# REPORT_flussimetro.net
KiCad netlist of a schematic drawn in EAGLE
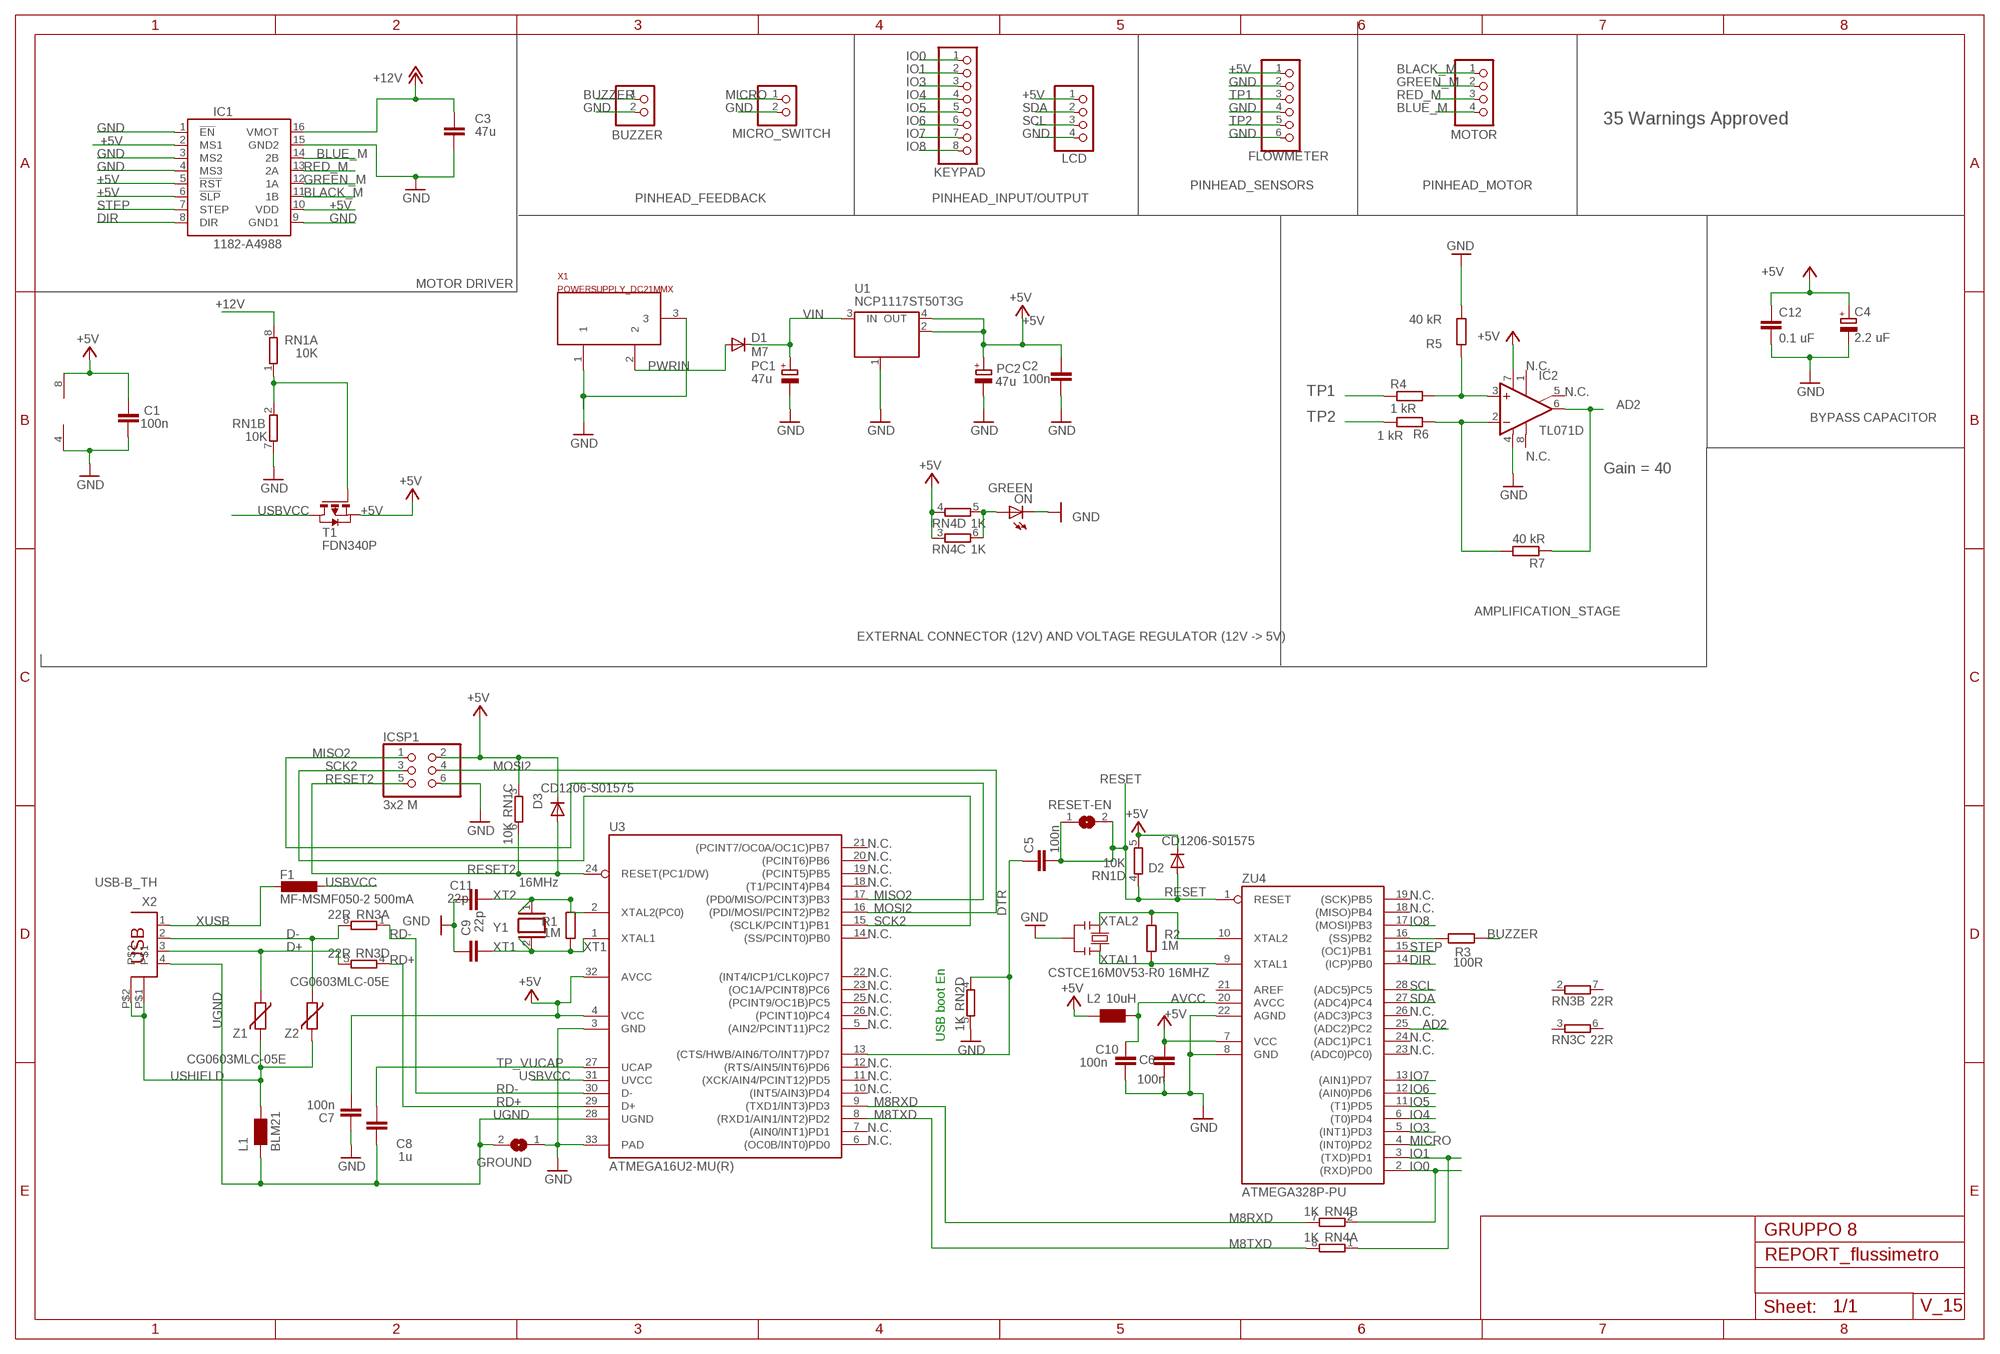
[diagram p0: schematic, sheet 1]

(export (version "E")
  (design (tool "Eeschema 10.0.6"))
  (components
    (comp (ref "BUZZER")
      (value "PINHD-1X2")
      (footprint "eagle-import:1X02")
      (fields (field (name "MF") "AMP - TE CONNECTIVITY") (field (name "MPN") "826926-2"))
      (libsource (lib "eagle-import") (part "PINHD-1X2"))
    )
    (comp (ref "C1")
      (value "100n")
      (footprint "eagle-import:C0603-ROUND")
      (fields (field (name "MF") "GEDORE") (field (name "MPN") "4550-10"))
      (libsource (lib "eagle-import") (part "C-EU0603-RND"))
    )
    (comp (ref "C2")
      (value "100n")
      (footprint "eagle-import:C0603-ROUND")
      (fields (field (name "MF") "GEDORE") (field (name "MPN") "4550-10"))
      (libsource (lib "eagle-import") (part "C-EU0603-RND"))
    )
    (comp (ref "C3")
      (value "47u")
      (footprint "eagle-import:C0603")
      (fields (field (name "MF") "MURATA") (field (name "MPN") "GRM188R60J476ME15D"))
      (libsource (lib "eagle-import") (part "rcl_334_C-EUC0603"))
    )
    (comp (ref "C4")
      (value "2.2 uF")
      (footprint "eagle-import:A_3216-18R")
      (fields (field (name "MF") "KYOCERA AVX") (field (name "MPN") "TAJA225K016RNJ"))
      (libsource (lib "eagle-import") (part "rcl_334_CPOL-EUA/3216-18R"))
    )
    (comp (ref "C5")
      (value "100n")
      (footprint "eagle-import:C0603-ROUND")
      (fields (field (name "MF") "GEDORE") (field (name "MPN") "4550-10"))
      (libsource (lib "eagle-import") (part "C-EU0603-RND"))
    )
    (comp (ref "C6")
      (value "100n")
      (footprint "eagle-import:C0603-ROUND")
      (fields (field (name "MF") "GEDORE") (field (name "MPN") "4550-10"))
      (libsource (lib "eagle-import") (part "C-EU0603-RND"))
    )
    (comp (ref "C7")
      (value "100n")
      (footprint "eagle-import:C0603-ROUND")
      (fields (field (name "MF") "GEDORE") (field (name "MPN") "4550-10"))
      (libsource (lib "eagle-import") (part "C-EU0603-RND"))
    )
    (comp (ref "C8")
      (value "1u")
      (footprint "eagle-import:C0603-ROUND")
      (fields (field (name "MF") "TDK") (field (name "MPN") "C1608X5R1C105K080AA"))
      (libsource (lib "eagle-import") (part "C-EU0603-RND"))
    )
    (comp (ref "C9")
      (value "22p")
      (footprint "eagle-import:C0603-ROUND")
      (fields (field (name "MF") "KYOCERA AVX") (field (name "MPN") "06035A220FAT2A"))
      (libsource (lib "eagle-import") (part "C-EU0603-RND"))
    )
    (comp (ref "C10")
      (value "100n")
      (footprint "eagle-import:C0603-ROUND")
      (fields (field (name "MF") "GEDORE") (field (name "MPN") "4550-10"))
      (libsource (lib "eagle-import") (part "C-EU0603-RND"))
    )
    (comp (ref "C11")
      (value "22p")
      (footprint "eagle-import:C0603-ROUND")
      (fields (field (name "MF") "KYOCERA AVX") (field (name "MPN") "06035A220FAT2A"))
      (libsource (lib "eagle-import") (part "C-EU0603-RND"))
    )
    (comp (ref "C12")
      (value "0.1 uF")
      (footprint "eagle-import:C0603")
      (fields (field (name "MF") "KYOCERA AVX") (field (name "MPN") "0603YC104KAT2A"))
      (libsource (lib "eagle-import") (part "rcl_334_C-EUC0603"))
    )
    (comp (ref "D1")
      (value "M7")
      (footprint "eagle-import:SMB")
      (fields (field (name "MF") "DIODES INC.") (field (name "MPN") "S1M-13-F"))
      (libsource (lib "eagle-import") (part "DIODE-SMB"))
    )
    (comp (ref "D2")
      (value "CD1206-S01575")
      (footprint "eagle-import:MINIMELF")
      (fields (field (name "MF") "BOURNS"))
      (libsource (lib "eagle-import") (part "DIODE-MINIMELF"))
    )
    (comp (ref "D3")
      (value "CD1206-S01575")
      (footprint "eagle-import:MINIMELF")
      (fields (field (name "MF") "BOURNS"))
      (libsource (lib "eagle-import") (part "DIODE-MINIMELF"))
    )
    (comp (ref "F1")
      (value "MF-MSMF050-2 500mA")
      (footprint "eagle-import:L1812")
      (fields (field (name "MF") "BOURNS") (field (name "MPN") "MF-MSMF050-2"))
      (libsource (lib "eagle-import") (part "L-EUL1812"))
    )
    (comp (ref "FLOWMETER")
      (value "PINHD-1X6")
      (footprint "eagle-import:1X06")
      (fields (field (name "MF") "MULTICOMP PRO") (field (name "MPN") "2211S-06G"))
      (libsource (lib "eagle-import") (part "PINHD-1X6"))
    )
    (comp (ref "GROUND")
      (value "SJ")
      (footprint "eagle-import:SJ")
      (libsource (lib "eagle-import") (part "SJ"))
    )
    (comp (ref "IC1")
      (value "1182-A4988")
      (footprint "eagle-import:A4988")
      (libsource (lib "eagle-import") (part "1182-A4988"))
    )
    (comp (ref "IC2")
      (value "TL071D")
      (footprint "eagle-import:SO08")
      (fields (field (name "MF") "ANALOG DEVICES") (field (name "MPN") "LT1211CS8#TRPBF"))
      (libsource (lib "eagle-import") (part "TL071D"))
    )
    (comp (ref "ICSP1")
      (value "3x2 M")
      (footprint "eagle-import:2X03")
      (fields (field (name "MF") "MOLEX") (field (name "MPN") "87758-0616"))
      (libsource (lib "eagle-import") (part "PINHD-2X3"))
    )
    (comp (ref "KEYPAD")
      (value "PINHD-1X8")
      (footprint "eagle-import:1X08")
      (fields (field (name "MF") "MULTICOMP PRO") (field (name "MPN") "2211S-08G"))
      (libsource (lib "eagle-import") (part "PINHD-1X8"))
    )
    (comp (ref "L1")
      (value "BLM21")
      (footprint "eagle-import:0805")
      (fields (field (name "MF") "MURATA") (field (name "MPN") "BLM21SP471BH1D"))
      (libsource (lib "eagle-import") (part "WE-CBF_0805"))
    )
    (comp (ref "L2")
      (value "10uH")
      (footprint "eagle-import:0805")
      (fields (field (name "PART_NUMBER") "CV201210-100K") (field (name "MF") "BOURNS"))
      (libsource (lib "eagle-import") (part "0715_CV201210-100K"))
    )
    (comp (ref "LCD")
      (value "PINHD-1X4")
      (footprint "eagle-import:1X04")
      (fields (field (name "MF") "AMP - TE CONNECTIVITY") (field (name "MPN") "826926-4"))
      (libsource (lib "eagle-import") (part "PINHD-1X4"))
    )
    (comp (ref "MICRO_SWITCH")
      (value "PINHD-1X2")
      (footprint "eagle-import:1X02")
      (fields (field (name "MF") "AMP - TE CONNECTIVITY") (field (name "MPN") "826926-2"))
      (libsource (lib "eagle-import") (part "PINHD-1X2"))
    )
    (comp (ref "MOTOR")
      (value "PINHD-1X4")
      (footprint "eagle-import:1X04")
      (fields (field (name "MF") "AMP - TE CONNECTIVITY") (field (name "MPN") "826926-4"))
      (libsource (lib "eagle-import") (part "PINHD-1X4"))
    )
    (comp (ref "ON")
      (value "GREEN")
      (footprint "eagle-import:CHIP-LED0805")
      (fields (field (name "MF") "KINGBRIGHT") (field (name "MPN") "KP-1608SGC"))
      (libsource (lib "eagle-import") (part "LEDCHIP-LED0805"))
    )
    (comp (ref "PC1")
      (value "47u")
      (footprint "eagle-import:PANASONIC_D")
      (fields (field (name "MF") "PANASONIC") (field (name "MPN") "EEE1EA470WP"))
      (libsource (lib "eagle-import") (part "CPOL-EUD"))
    )
    (comp (ref "PC2")
      (value "47u")
      (footprint "eagle-import:PANASONIC_D")
      (fields (field (name "MF") "PANASONIC") (field (name "MPN") "EEE1EA470WP"))
      (libsource (lib "eagle-import") (part "CPOL-EUD"))
    )
    (comp (ref "R1")
      (value "1M")
      (footprint "eagle-import:R0603-ROUND")
      (fields (field (name "MF") "TE CONNECTIVITY") (field (name "MPN") "CRGH0603J1M0"))
      (libsource (lib "eagle-import") (part "R-EU_R0603"))
    )
    (comp (ref "R2")
      (value "1M")
      (footprint "eagle-import:R0603-ROUND")
      (fields (field (name "MF") "TE CONNECTIVITY") (field (name "MPN") "CRGH0603J1M0"))
      (libsource (lib "eagle-import") (part "R-EU_R0603"))
    )
    (comp (ref "R3")
      (value "100R")
      (footprint "eagle-import:R0603")
      (fields (field (name "MF") "PANASONIC") (field (name "MPN") "ERJPA3F1000V"))
      (libsource (lib "eagle-import") (part "rcl_334_R-EU_R0603"))
    )
    (comp (ref "R4")
      (value "1 kR")
      (footprint "eagle-import:R0603")
      (fields (field (name "MF") "NEOHM - TE CONNECTIVITY") (field (name "MPN") "CPF0603B1K0E1"))
      (libsource (lib "eagle-import") (part "rcl_334_R-EU_R0603"))
    )
    (comp (ref "R5")
      (value "40 kR")
      (footprint "eagle-import:R0603")
      (fields (field (name "MF") "YAGEO") (field (name "MPN") "AT0603BRD0740KL"))
      (libsource (lib "eagle-import") (part "rcl_334_R-EU_R0603"))
    )
    (comp (ref "R6")
      (value "1 kR")
      (footprint "eagle-import:R0603")
      (fields (field (name "MF") "NEOHM - TE CONNECTIVITY") (field (name "MPN") "CPF0603B1K0E1"))
      (libsource (lib "eagle-import") (part "rcl_334_R-EU_R0603"))
    )
    (comp (ref "R7")
      (value "40 kR")
      (footprint "eagle-import:R0603")
      (fields (field (name "MF") "YAGEO") (field (name "MPN") "AT0603BRD0740KL"))
      (libsource (lib "eagle-import") (part "rcl_334_R-EU_R0603"))
    )
    (comp (ref "RESET-EN")
      (value "SJ")
      (footprint "eagle-import:SJ")
      (libsource (lib "eagle-import") (part "SJ"))
    )
    (comp (ref "RN1")
      (value "10K")
      (footprint "eagle-import:CAY16")
      (fields
        (field (name "MF") "BOURNS")
        (field (name "MPN") "CAY16-1002F4LF")
        (field (name "OC_FARNELL") "1770143")
      )
      (libsource (lib "eagle-import") (part "4R-NCAY16"))
    )
    (comp (ref "RN2")
      (value "1K")
      (footprint "eagle-import:CAY16")
      (fields (field (name "MF") "BOURNS") (field (name "MPN") "CAY16-102J4LF"))
      (libsource (lib "eagle-import") (part "4R-NCAY16"))
    )
    (comp (ref "RN3")
      (value "22R")
      (footprint "eagle-import:CAY16")
      (fields
        (field (name "MF") "BOURNS")
        (field (name "MPN") "CAY16-220J4LF")
        (field (name "OC_FARNELL") "1770127")
      )
      (libsource (lib "eagle-import") (part "4R-NCAY16"))
    )
    (comp (ref "RN4")
      (value "1K")
      (footprint "eagle-import:CAY16")
      (fields
        (field (name "MF") "BOURNS")
        (field (name "MPN") "CAY16-102J4LF")
        (field (name "OC_FARNELL") "1770133")
      )
      (libsource (lib "eagle-import") (part "4R-NCAY16"))
    )
    (comp (ref "T1")
      (value "FDN340P")
      (footprint "eagle-import:SOT-23")
      (fields (field (name "MF") "ONSEMI"))
      (libsource (lib "eagle-import") (part "PMOSSOT23"))
    )
    (comp (ref "U1")
      (value "NCP1117ST50T3G")
      (footprint "eagle-import:SOT223")
      (fields (field (name "MF") "ONSEMI"))
      (libsource (lib "eagle-import") (part "MC33269ST-3.3T3"))
    )
    (comp (ref "U3")
      (value "ATMEGA16U2-MU(R)")
      (footprint "eagle-import:MLF32")
      (fields (field (name "MF") "MICROCHIP") (field (name "MPN") "ATMEGA16U2-MUR"))
      (libsource (lib "eagle-import") (part "ATMEGA16U2-MU"))
    )
    (comp (ref "U5")
      (value "LMV358IDGKR")
      (footprint "eagle-import:MSOP08")
      (fields (field (name "MF") "STMICROELECTRONICS") (field (name "MPN") "LMV358LIST"))
      (libsource (lib "eagle-import") (part "LMV358?MMX"))
    )
    (comp (ref "X1")
      (value "POWERSUPPLY_DC21MMX")
      (footprint "eagle-import:POWERSUPPLY_DC-21MM")
      (fields (field (name "MF") "LUMBERG") (field (name "MPN") "1613 21"))
      (libsource (lib "eagle-import") (part "POWERSUPPLY_DC21MMX"))
    )
    (comp (ref "X2")
      (value "USB-B_TH")
      (footprint "eagle-import:PN61729")
      (fields (field (name "MF") "MULTICOMP PRO") (field (name "MPN") "SPC4937"))
      (libsource (lib "eagle-import") (part "PN61729"))
    )
    (comp (ref "Y1")
      (value "16MHz")
      (footprint "eagle-import:QS")
      (fields (field (name "MF") "ECS INC INTERNATIONAL") (field (name "MPN") "ECS-160-20-4X"))
      (libsource (lib "eagle-import") (part "XTAL/S"))
    )
    (comp (ref "Y2")
      (value "CSTCE16M0V53-R0 16MHZ")
      (footprint "eagle-import:RESONATOR")
      (fields (field (name "MF") "MURATA") (field (name "MPN") "CSTNE16M0V51C000R0"))
      (libsource (lib "eagle-import") (part "RESONATORMU"))
    )
    (comp (ref "Z1")
      (value "CG0603MLC-05E")
      (footprint "eagle-import:CT_CN0603")
      (fields (field (name "MF") "BOURNS"))
      (libsource (lib "eagle-import") (part "VARISTORCN0603"))
    )
    (comp (ref "Z2")
      (value "CG0603MLC-05E")
      (footprint "eagle-import:CT_CN0603")
      (fields (field (name "MF") "BOURNS"))
      (libsource (lib "eagle-import") (part "VARISTORCN0603"))
    )
    (comp (ref "ZU4")
      (value "ATMEGA328P-PU")
      (footprint "eagle-import:DIL28-3")
      (fields (field (name "MF") "MICROCHIP"))
      (libsource (lib "eagle-import") (part "ATMEGA328P-PU"))
    )
  )
  (nets
    (net (code "1") (name "+5V") (class "Default")
      (node (ref "C1") (pin "2") (pinfunction "2_2") (pintype "passive"))
      (node (ref "C12") (pin "1") (pinfunction "1_1") (pintype "passive"))
      (node (ref "C2") (pin "2") (pinfunction "2_2") (pintype "passive"))
      (node (ref "C4") (pin "+") (pinfunction "+_+") (pintype "passive"))
      (node (ref "C6") (pin "2") (pinfunction "2_2") (pintype "passive"))
      (node (ref "C7") (pin "1") (pinfunction "1_1") (pintype "passive"))
      (node (ref "D2") (pin "C") (pinfunction "C_C") (pintype "passive"))
      (node (ref "D3") (pin "C") (pinfunction "C_C") (pintype "passive"))
      (node (ref "FLOWMETER") (pin "1") (pinfunction "1_1") (pintype "passive"))
      (node (ref "IC1") (pin "10") (pinfunction "VDD_10") (pintype "power_in"))
      (node (ref "IC1") (pin "2") (pinfunction "MS1_2") (pintype "passive"))
      (node (ref "IC1") (pin "5") (pinfunction "~{RST}_5") (pintype "passive"))
      (node (ref "IC1") (pin "6") (pinfunction "~{SLP}_6") (pintype "passive"))
      (node (ref "IC2") (pin "7") (pinfunction "V+_7") (pintype "power_in"))
      (node (ref "ICSP1") (pin "2") (pinfunction "2_2") (pintype "passive"))
      (node (ref "L2") (pin "1") (pinfunction "1_1") (pintype "passive"))
      (node (ref "LCD") (pin "1") (pinfunction "1_1") (pintype "passive"))
      (node (ref "PC2") (pin "+") (pinfunction "+_+") (pintype "passive"))
      (node (ref "RN1") (pin "1") (pinfunction "1_1") (pintype "passive"))
      (node (ref "RN1") (pin "2") (pinfunction "1_2") (pintype "passive"))
      (node (ref "RN1") (pin "3") (pinfunction "1_3") (pintype "passive"))
      (node (ref "RN1") (pin "5") (pinfunction "2_5") (pintype "passive"))
      (node (ref "RN4") (pin "3") (pinfunction "1_3") (pintype "passive"))
      (node (ref "RN4") (pin "4") (pinfunction "1_4") (pintype "passive"))
      (node (ref "T1") (pin "2") (pinfunction "S_2") (pintype "passive"))
      (node (ref "T1") (pin "3") (pinfunction "G_3") (pintype "passive"))
      (node (ref "U1") (pin "2") (pinfunction "OUT_2") (pintype "passive"))
      (node (ref "U1") (pin "4") (pinfunction "OUT_4") (pintype "passive"))
      (node (ref "U3") (pin "32") (pinfunction "AVCC_32") (pintype "power_in"))
      (node (ref "U3") (pin "4") (pinfunction "VCC_4") (pintype "power_in"))
      (node (ref "U5") (pin "8") (pinfunction "V+_8") (pintype "power_in"))
      (node (ref "ZU4") (pin "7") (pinfunction "VCC_7") (pintype "power_in"))
    )
    (net (code "2") (name "+12V") (class "Default")
      (node (ref "C3") (pin "1") (pinfunction "1_1") (pintype "passive"))
      (node (ref "IC1") (pin "16") (pinfunction "VMOT_16") (pintype "power_in"))
      (node (ref "RN1") (pin "8") (pinfunction "2_8") (pintype "passive"))
    )
    (net (code "3") (name "/AD2") (class "Default")
      (node (ref "IC2") (pin "6") (pinfunction "OUT_6") (pintype "output"))
      (node (ref "R7") (pin "1") (pinfunction "1_1") (pintype "passive"))
      (node (ref "ZU4") (pin "25") (pinfunction "(ADC2)PC2_25") (pintype "bidirectional"))
    )
    (net (code "4") (name "/AVCC") (class "Default")
      (node (ref "C10") (pin "2") (pinfunction "2_2") (pintype "passive"))
      (node (ref "L2") (pin "2") (pinfunction "2_2") (pintype "passive"))
      (node (ref "ZU4") (pin "20") (pinfunction "AVCC_20") (pintype "power_in"))
    )
    (net (code "5") (name "/BLACK_M") (class "Default")
      (node (ref "IC1") (pin "11") (pinfunction "1B_11") (pintype "output"))
      (node (ref "MOTOR") (pin "1") (pinfunction "1_1") (pintype "passive"))
    )
    (net (code "6") (name "/BLUE_M") (class "Default")
      (node (ref "IC1") (pin "14") (pinfunction "2B_14") (pintype "output"))
      (node (ref "MOTOR") (pin "4") (pinfunction "4_4") (pintype "passive"))
    )
    (net (code "7") (name "/BUZZER") (class "Default")
      (node (ref "BUZZER") (pin "1") (pinfunction "1_1") (pintype "passive"))
      (node (ref "R3") (pin "2") (pinfunction "2_2") (pintype "passive"))
    )
    (net (code "8") (name "/D+") (class "Default")
      (node (ref "RN3") (pin "5") (pinfunction "2_5") (pintype "passive"))
      (node (ref "X2") (pin "3") (pinfunction "3_3") (pintype "bidirectional"))
      (node (ref "Z1") (pin "1") (pinfunction "1_1") (pintype "passive"))
    )
    (net (code "9") (name "/D-") (class "Default")
      (node (ref "RN3") (pin "8") (pinfunction "2_8") (pintype "passive"))
      (node (ref "X2") (pin "2") (pinfunction "2_2") (pintype "bidirectional"))
      (node (ref "Z2") (pin "1") (pinfunction "1_1") (pintype "passive"))
    )
    (net (code "10") (name "/DIR") (class "Default")
      (node (ref "IC1") (pin "8") (pinfunction "DIR_8") (pintype "input"))
      (node (ref "ZU4") (pin "14") (pinfunction "(ICP)PB0_14") (pintype "bidirectional"))
    )
    (net (code "11") (name "/DTR") (class "Default")
      (node (ref "C5") (pin "1") (pinfunction "1_1") (pintype "passive"))
      (node (ref "RN2") (pin "4") (pinfunction "1_4") (pintype "passive"))
      (node (ref "U3") (pin "13") (pinfunction "(CTS/HWB/AIN6/TO/INT7)PD7_13") (pintype "bidirectional"))
    )
    (net (code "12") (name "/GREEN_M") (class "Default")
      (node (ref "IC1") (pin "12") (pinfunction "1A_12") (pintype "output"))
      (node (ref "MOTOR") (pin "2") (pinfunction "2_2") (pintype "passive"))
    )
    (net (code "13") (name "/IO0") (class "Default")
      (node (ref "KEYPAD") (pin "1") (pinfunction "1_1") (pintype "passive"))
      (node (ref "RN4") (pin "2") (pinfunction "1_2") (pintype "passive"))
      (node (ref "ZU4") (pin "2") (pinfunction "(RXD)PD0_2") (pintype "bidirectional"))
    )
    (net (code "14") (name "/IO1") (class "Default")
      (node (ref "KEYPAD") (pin "2") (pinfunction "2_2") (pintype "passive"))
      (node (ref "RN4") (pin "1") (pinfunction "1_1") (pintype "passive"))
      (node (ref "ZU4") (pin "3") (pinfunction "(TXD)PD1_3") (pintype "bidirectional"))
    )
    (net (code "15") (name "/IO3") (class "Default")
      (node (ref "KEYPAD") (pin "3") (pinfunction "3_3") (pintype "passive"))
      (node (ref "ZU4") (pin "5") (pinfunction "(INT1)PD3_5") (pintype "bidirectional"))
    )
    (net (code "16") (name "/IO4") (class "Default")
      (node (ref "KEYPAD") (pin "4") (pinfunction "4_4") (pintype "passive"))
      (node (ref "ZU4") (pin "6") (pinfunction "(T0)PD4_6") (pintype "bidirectional"))
    )
    (net (code "17") (name "/IO5") (class "Default")
      (node (ref "KEYPAD") (pin "5") (pinfunction "5_5") (pintype "passive"))
      (node (ref "ZU4") (pin "11") (pinfunction "(T1)PD5_11") (pintype "bidirectional"))
    )
    (net (code "18") (name "/IO6") (class "Default")
      (node (ref "KEYPAD") (pin "6") (pinfunction "6_6") (pintype "passive"))
      (node (ref "ZU4") (pin "12") (pinfunction "(AIN0)PD6_12") (pintype "bidirectional"))
    )
    (net (code "19") (name "/IO7") (class "Default")
      (node (ref "KEYPAD") (pin "7") (pinfunction "7_7") (pintype "passive"))
      (node (ref "ZU4") (pin "13") (pinfunction "(AIN1)PD7_13") (pintype "bidirectional"))
    )
    (net (code "20") (name "/IO8") (class "Default")
      (node (ref "KEYPAD") (pin "8") (pinfunction "8_8") (pintype "passive"))
      (node (ref "ZU4") (pin "17") (pinfunction "(MOSI)PB3_17") (pintype "bidirectional"))
    )
    (net (code "21") (name "/M8RXD") (class "Default")
      (node (ref "RN4") (pin "7") (pinfunction "2_7") (pintype "passive"))
      (node (ref "U3") (pin "9") (pinfunction "(TXD1/INT3)PD3_9") (pintype "bidirectional"))
    )
    (net (code "22") (name "/M8TXD") (class "Default")
      (node (ref "RN4") (pin "8") (pinfunction "2_8") (pintype "passive"))
      (node (ref "U3") (pin "8") (pinfunction "(RXD1/AIN1/INT2)PD2_8") (pintype "bidirectional"))
    )
    (net (code "23") (name "/MICRO") (class "Default")
      (node (ref "MICRO_SWITCH") (pin "1") (pinfunction "1_1") (pintype "passive"))
      (node (ref "ZU4") (pin "4") (pinfunction "(INT0)PD2_4") (pintype "bidirectional"))
    )
    (net (code "24") (name "/MISO2") (class "Default")
      (node (ref "ICSP1") (pin "1") (pinfunction "1_1") (pintype "passive"))
      (node (ref "U3") (pin "17") (pinfunction "(PD0/MISO/PCINT3)PB3_17") (pintype "bidirectional"))
    )
    (net (code "25") (name "/MOSI2") (class "Default")
      (node (ref "ICSP1") (pin "4") (pinfunction "4_4") (pintype "passive"))
      (node (ref "U3") (pin "16") (pinfunction "(PDI/MOSI/PCINT2)PB2_16") (pintype "bidirectional"))
    )
    (net (code "26") (name "/PWRIN") (class "Default")
      (node (ref "D1") (pin "A") (pinfunction "A_A") (pintype "passive"))
      (node (ref "X1") (pin "2") (pinfunction "2_2") (pintype "power_in"))
    )
    (net (code "27") (name "/RD+") (class "Default")
      (node (ref "RN3") (pin "4") (pinfunction "1_4") (pintype "passive"))
      (node (ref "U3") (pin "29") (pinfunction "D+_29") (pintype "bidirectional"))
    )
    (net (code "28") (name "/RD-") (class "Default")
      (node (ref "RN3") (pin "1") (pinfunction "1_1") (pintype "passive"))
      (node (ref "U3") (pin "30") (pinfunction "D-_30") (pintype "bidirectional"))
    )
    (net (code "29") (name "/RED_M") (class "Default")
      (node (ref "IC1") (pin "13") (pinfunction "2A_13") (pintype "output"))
      (node (ref "MOTOR") (pin "3") (pinfunction "3_3") (pintype "passive"))
    )
    (net (code "30") (name "/RESET") (class "Default")
      (node (ref "C5") (pin "2") (pinfunction "2_2") (pintype "passive"))
      (node (ref "D2") (pin "A") (pinfunction "A_A") (pintype "passive"))
      (node (ref "RESET-EN") (pin "1") (pinfunction "1_1") (pintype "passive"))
      (node (ref "RESET-EN") (pin "2") (pinfunction "2_2") (pintype "passive"))
      (node (ref "RN1") (pin "4") (pinfunction "1_4") (pintype "passive"))
      (node (ref "ZU4") (pin "1") (pinfunction "RESET_1") (pintype "input"))
    )
    (net (code "31") (name "/RESET2") (class "Default")
      (node (ref "D3") (pin "A") (pinfunction "A_A") (pintype "passive"))
      (node (ref "ICSP1") (pin "5") (pinfunction "5_5") (pintype "passive"))
      (node (ref "RN1") (pin "6") (pinfunction "2_6") (pintype "passive"))
      (node (ref "U3") (pin "24") (pinfunction "RESET(PC1/DW)_24") (pintype "input"))
    )
    (net (code "32") (name "/SCK2") (class "Default")
      (node (ref "ICSP1") (pin "3") (pinfunction "3_3") (pintype "passive"))
      (node (ref "U3") (pin "15") (pinfunction "(SCLK/PCINT1)PB1_15") (pintype "bidirectional"))
    )
    (net (code "33") (name "/SCL") (class "Default")
      (node (ref "LCD") (pin "3") (pinfunction "3_3") (pintype "passive"))
      (node (ref "ZU4") (pin "28") (pinfunction "(ADC5)PC5_28") (pintype "bidirectional"))
    )
    (net (code "34") (name "/SDA") (class "Default")
      (node (ref "LCD") (pin "2") (pinfunction "2_2") (pintype "passive"))
      (node (ref "ZU4") (pin "27") (pinfunction "(ADC4)PC4_27") (pintype "bidirectional"))
    )
    (net (code "35") (name "/STEP") (class "Default")
      (node (ref "IC1") (pin "7") (pinfunction "STEP_7") (pintype "input"))
      (node (ref "ZU4") (pin "15") (pinfunction "(OC1)PB1_15") (pintype "bidirectional"))
    )
    (net (code "36") (name "/TP1") (class "Default")
      (node (ref "FLOWMETER") (pin "3") (pinfunction "3_3") (pintype "passive"))
      (node (ref "R4") (pin "1") (pinfunction "1_1") (pintype "passive"))
    )
    (net (code "37") (name "/TP2") (class "Default")
      (node (ref "FLOWMETER") (pin "5") (pinfunction "5_5") (pintype "passive"))
      (node (ref "R6") (pin "2") (pinfunction "2_2") (pintype "passive"))
    )
    (net (code "38") (name "/TP_VUCAP") (class "Default")
      (node (ref "C8") (pin "1") (pinfunction "1_1") (pintype "passive"))
      (node (ref "U3") (pin "27") (pinfunction "UCAP_27") (pintype "passive"))
    )
    (net (code "39") (name "/UGND") (class "Default")
      (node (ref "C8") (pin "2") (pinfunction "2_2") (pintype "passive"))
      (node (ref "GROUND") (pin "2") (pinfunction "2_2") (pintype "passive"))
      (node (ref "L1") (pin "1") (pinfunction "1_1") (pintype "passive"))
      (node (ref "U3") (pin "28") (pinfunction "UGND_28") (pintype "power_in"))
      (node (ref "X2") (pin "4") (pinfunction "4_4") (pintype "bidirectional"))
    )
    (net (code "40") (name "/USBVCC") (class "Default")
      (node (ref "F1") (pin "1") (pinfunction "1_1") (pintype "passive"))
      (node (ref "T1") (pin "1") (pinfunction "D_1") (pintype "passive"))
      (node (ref "U3") (pin "31") (pinfunction "UVCC_31") (pintype "power_in"))
    )
    (net (code "41") (name "/USHIELD") (class "Default")
      (node (ref "L1") (pin "2") (pinfunction "2_2") (pintype "passive"))
      (node (ref "X2") (pin "P$1") (pinfunction "P$1_P$1") (pintype "bidirectional"))
      (node (ref "X2") (pin "P$2") (pinfunction "P$2_P$2") (pintype "bidirectional"))
      (node (ref "Z1") (pin "2") (pinfunction "2_2") (pintype "passive"))
      (node (ref "Z2") (pin "2") (pinfunction "2_2") (pintype "passive"))
    )
    (net (code "42") (name "/VIN") (class "Default")
      (node (ref "D1") (pin "C") (pinfunction "C_C") (pintype "passive"))
      (node (ref "PC1") (pin "+") (pinfunction "+_+") (pintype "passive"))
      (node (ref "U1") (pin "3") (pinfunction "IN_3") (pintype "input"))
    )
    (net (code "43") (name "/XT1") (class "Default")
      (node (ref "C9") (pin "1") (pinfunction "1_1") (pintype "passive"))
      (node (ref "R1") (pin "1") (pinfunction "1_1") (pintype "passive"))
      (node (ref "U3") (pin "1") (pinfunction "XTAL1_1") (pintype "bidirectional"))
      (node (ref "Y1") (pin "2") (pinfunction "2_2") (pintype "passive"))
    )
    (net (code "44") (name "/XT2") (class "Default")
      (node (ref "C11") (pin "1") (pinfunction "1_1") (pintype "passive"))
      (node (ref "R1") (pin "2") (pinfunction "2_2") (pintype "passive"))
      (node (ref "U3") (pin "2") (pinfunction "XTAL2(PC0)_2") (pintype "bidirectional"))
      (node (ref "Y1") (pin "1") (pinfunction "1_1") (pintype "passive"))
    )
    (net (code "45") (name "/XTAL1") (class "Default")
      (node (ref "R2") (pin "1") (pinfunction "1_1") (pintype "passive"))
      (node (ref "Y2") (pin "3") (pinfunction "3_3") (pintype "passive"))
      (node (ref "ZU4") (pin "9") (pinfunction "XTAL1_9") (pintype "bidirectional"))
    )
    (net (code "46") (name "/XTAL2") (class "Default")
      (node (ref "R2") (pin "2") (pinfunction "2_2") (pintype "passive"))
      (node (ref "Y2") (pin "1") (pinfunction "1_1") (pintype "passive"))
      (node (ref "ZU4") (pin "10") (pinfunction "XTAL2_10") (pintype "bidirectional"))
    )
    (net (code "47") (name "/XUSB") (class "Default")
      (node (ref "F1") (pin "2") (pinfunction "2_2") (pintype "passive"))
      (node (ref "X2") (pin "1") (pinfunction "1_1") (pintype "bidirectional"))
    )
    (net (code "48") (name "GND") (class "Default")
      (node (ref "BUZZER") (pin "2") (pinfunction "2_2") (pintype "passive"))
      (node (ref "C1") (pin "1") (pinfunction "1_1") (pintype "passive"))
      (node (ref "C10") (pin "1") (pinfunction "1_1") (pintype "passive"))
      (node (ref "C11") (pin "2") (pinfunction "2_2") (pintype "passive"))
      (node (ref "C12") (pin "2") (pinfunction "2_2") (pintype "passive"))
      (node (ref "C2") (pin "1") (pinfunction "1_1") (pintype "passive"))
      (node (ref "C3") (pin "2") (pinfunction "2_2") (pintype "passive"))
      (node (ref "C4") (pin "-") (pinfunction "-_-") (pintype "passive"))
      (node (ref "C6") (pin "1") (pinfunction "1_1") (pintype "passive"))
      (node (ref "C7") (pin "2") (pinfunction "2_2") (pintype "passive"))
      (node (ref "C9") (pin "2") (pinfunction "2_2") (pintype "passive"))
      (node (ref "FLOWMETER") (pin "2") (pinfunction "2_2") (pintype "passive"))
      (node (ref "FLOWMETER") (pin "4") (pinfunction "4_4") (pintype "passive"))
      (node (ref "FLOWMETER") (pin "6") (pinfunction "6_6") (pintype "passive"))
      (node (ref "GROUND") (pin "1") (pinfunction "1_1") (pintype "passive"))
      (node (ref "IC1") (pin "1") (pinfunction "~{EN}_1") (pintype "passive"))
      (node (ref "IC1") (pin "15") (pinfunction "GND2_15") (pintype "power_in"))
      (node (ref "IC1") (pin "3") (pinfunction "MS2_3") (pintype "passive"))
      (node (ref "IC1") (pin "4") (pinfunction "MS3_4") (pintype "passive"))
      (node (ref "IC1") (pin "9") (pinfunction "GND1_9") (pintype "power_in"))
      (node (ref "IC2") (pin "4") (pinfunction "V-_4") (pintype "power_in"))
      (node (ref "ICSP1") (pin "6") (pinfunction "6_6") (pintype "passive"))
      (node (ref "LCD") (pin "4") (pinfunction "4_4") (pintype "passive"))
      (node (ref "MICRO_SWITCH") (pin "2") (pinfunction "2_2") (pintype "passive"))
      (node (ref "ON") (pin "C") (pinfunction "C_C") (pintype "passive"))
      (node (ref "PC1") (pin "-") (pinfunction "-_-") (pintype "passive"))
      (node (ref "PC2") (pin "-") (pinfunction "-_-") (pintype "passive"))
      (node (ref "R5") (pin "2") (pinfunction "2_2") (pintype "passive"))
      (node (ref "RN1") (pin "7") (pinfunction "2_7") (pintype "passive"))
      (node (ref "RN2") (pin "5") (pinfunction "2_5") (pintype "passive"))
      (node (ref "U1") (pin "1") (pinfunction "GND/ADJ_1") (pintype "input"))
      (node (ref "U3") (pin "3") (pinfunction "GND_3") (pintype "power_in"))
      (node (ref "U3") (pin "33") (pinfunction "PAD_33") (pintype "power_in"))
      (node (ref "U5") (pin "4") (pinfunction "V-_4") (pintype "power_in"))
      (node (ref "X1") (pin "1") (pinfunction "1_1") (pintype "power_in"))
      (node (ref "X1") (pin "3") (pinfunction "3_3") (pintype "power_in"))
      (node (ref "Y2") (pin "2") (pinfunction "2_2") (pintype "passive"))
      (node (ref "ZU4") (pin "22") (pinfunction "AGND_22") (pintype "power_in"))
      (node (ref "ZU4") (pin "8") (pinfunction "GND_8") (pintype "power_in"))
    )
    (net (code "49") (name "Net-(IC2-+IN)") (class "Default")
      (node (ref "IC2") (pin "3") (pinfunction "+IN_3") (pintype "input"))
      (node (ref "R4") (pin "2") (pinfunction "2_2") (pintype "passive"))
      (node (ref "R5") (pin "1") (pinfunction "1_1") (pintype "passive"))
    )
    (net (code "50") (name "Net-(IC2--IN)") (class "Default")
      (node (ref "IC2") (pin "2") (pinfunction "-IN_2") (pintype "input"))
      (node (ref "R6") (pin "1") (pinfunction "1_1") (pintype "passive"))
      (node (ref "R7") (pin "2") (pinfunction "2_2") (pintype "passive"))
    )
    (net (code "51") (name "Net-(RN4C-2)") (class "Default")
      (node (ref "ON") (pin "A") (pinfunction "A_A") (pintype "passive"))
      (node (ref "RN4") (pin "5") (pinfunction "2_5") (pintype "passive"))
      (node (ref "RN4") (pin "6") (pinfunction "2_6") (pintype "passive"))
    )
    (net (code "52") (name "Net-(ZU4-(SS)PB2)") (class "Default")
      (node (ref "R3") (pin "1") (pinfunction "1_1") (pintype "passive"))
      (node (ref "ZU4") (pin "16") (pinfunction "(SS)PB2_16") (pintype "bidirectional"))
    )
    (net (code "53") (name "unconnected-(IC2-ON1-Pad1)") (class "Default")
      (node (ref "IC2") (pin "1") (pinfunction "ON1_1") (pintype "passive"))
    )
    (net (code "54") (name "unconnected-(IC2-ON2-Pad5)") (class "Default")
      (node (ref "IC2") (pin "5") (pinfunction "ON2_5") (pintype "passive"))
    )
    (net (code "55") (name "unconnected-(IC2-OPT-Pad8)") (class "Default")
      (node (ref "IC2") (pin "8") (pinfunction "OPT_8") (pintype "passive"))
    )
    (net (code "56") (name "unconnected-(RN3B-1-Pad2)") (class "Default")
      (node (ref "RN3") (pin "2") (pinfunction "1_2") (pintype "passive"))
    )
    (net (code "57") (name "unconnected-(RN3B-2-Pad7)") (class "Default")
      (node (ref "RN3") (pin "7") (pinfunction "2_7") (pintype "passive"))
    )
    (net (code "58") (name "unconnected-(RN3C-1-Pad3)") (class "Default")
      (node (ref "RN3") (pin "3") (pinfunction "1_3") (pintype "passive"))
    )
    (net (code "59") (name "unconnected-(RN3C-2-Pad6)") (class "Default")
      (node (ref "RN3") (pin "6") (pinfunction "2_6") (pintype "passive"))
    )
    (net (code "60") (name "unconnected-(U3-(AIN0{slash}INT1)PD1-Pad7)") (class "Default")
      (node (ref "U3") (pin "7") (pinfunction "(AIN0/INT1)PD1_7") (pintype "bidirectional"))
    )
    (net (code "61") (name "unconnected-(U3-(AIN2{slash}PCINT11)PC2-Pad5)") (class "Default")
      (node (ref "U3") (pin "5") (pinfunction "(AIN2/PCINT11)PC2_5") (pintype "bidirectional"))
    )
    (net (code "62") (name "unconnected-(U3-(INT4{slash}ICP1{slash}CLK0)PC7-Pad22)") (class "Default")
      (node (ref "U3") (pin "22") (pinfunction "(INT4/ICP1/CLK0)PC7_22") (pintype "bidirectional"))
    )
    (net (code "63") (name "unconnected-(U3-(INT5{slash}AIN3)PD4-Pad10)") (class "Default")
      (node (ref "U3") (pin "10") (pinfunction "(INT5/AIN3)PD4_10") (pintype "bidirectional"))
    )
    (net (code "64") (name "unconnected-(U3-(OC0B{slash}INT0)PD0-Pad6)") (class "Default")
      (node (ref "U3") (pin "6") (pinfunction "(OC0B/INT0)PD0_6") (pintype "bidirectional"))
    )
    (net (code "65") (name "unconnected-(U3-(OC1A{slash}PCINT8)PC6-Pad23)") (class "Default")
      (node (ref "U3") (pin "23") (pinfunction "(OC1A/PCINT8)PC6_23") (pintype "bidirectional"))
    )
    (net (code "66") (name "unconnected-(U3-(PCINT5)PB5-Pad19)") (class "Default")
      (node (ref "U3") (pin "19") (pinfunction "(PCINT5)PB5_19") (pintype "bidirectional"))
    )
    (net (code "67") (name "unconnected-(U3-(PCINT6)PB6-Pad20)") (class "Default")
      (node (ref "U3") (pin "20") (pinfunction "(PCINT6)PB6_20") (pintype "bidirectional"))
    )
    (net (code "68") (name "unconnected-(U3-(PCINT7{slash}OC0A{slash}OC1C)PB7-Pad21)") (class "Default")
      (node (ref "U3") (pin "21") (pinfunction "(PCINT7/OC0A/OC1C)PB7_21") (pintype "bidirectional"))
    )
    (net (code "69") (name "unconnected-(U3-(PCINT9{slash}OC1B)PC5-Pad25)") (class "Default")
      (node (ref "U3") (pin "25") (pinfunction "(PCINT9/OC1B)PC5_25") (pintype "bidirectional"))
    )
    (net (code "70") (name "unconnected-(U3-(PCINT10)PC4-Pad26)") (class "Default")
      (node (ref "U3") (pin "26") (pinfunction "(PCINT10)PC4_26") (pintype "bidirectional"))
    )
    (net (code "71") (name "unconnected-(U3-(RTS{slash}AIN5{slash}INT6)PD6-Pad12)") (class "Default")
      (node (ref "U3") (pin "12") (pinfunction "(RTS/AIN5/INT6)PD6_12") (pintype "bidirectional"))
    )
    (net (code "72") (name "unconnected-(U3-(SS{slash}PCINT0)PB0-Pad14)") (class "Default")
      (node (ref "U3") (pin "14") (pinfunction "(SS/PCINT0)PB0_14") (pintype "bidirectional"))
    )
    (net (code "73") (name "unconnected-(U3-(T1{slash}PCINT4)PB4-Pad18)") (class "Default")
      (node (ref "U3") (pin "18") (pinfunction "(T1/PCINT4)PB4_18") (pintype "bidirectional"))
    )
    (net (code "74") (name "unconnected-(U3-(XCK{slash}AIN4{slash}PCINT12)PD5-Pad11)") (class "Default")
      (node (ref "U3") (pin "11") (pinfunction "(XCK/AIN4/PCINT12)PD5_11") (pintype "bidirectional"))
    )
    (net (code "75") (name "unconnected-(ZU4-(ADC0)PC0)-Pad23)") (class "Default")
      (node (ref "ZU4") (pin "23") (pinfunction "(ADC0)PC0)_23") (pintype "bidirectional"))
    )
    (net (code "76") (name "unconnected-(ZU4-(ADC1)PC1-Pad24)") (class "Default")
      (node (ref "ZU4") (pin "24") (pinfunction "(ADC1)PC1_24") (pintype "bidirectional"))
    )
    (net (code "77") (name "unconnected-(ZU4-(ADC3)PC3-Pad26)") (class "Default")
      (node (ref "ZU4") (pin "26") (pinfunction "(ADC3)PC3_26") (pintype "bidirectional"))
    )
    (net (code "78") (name "unconnected-(ZU4-(MISO)PB4-Pad18)") (class "Default")
      (node (ref "ZU4") (pin "18") (pinfunction "(MISO)PB4_18") (pintype "bidirectional"))
    )
    (net (code "79") (name "unconnected-(ZU4-(SCK)PB5-Pad19)") (class "Default")
      (node (ref "ZU4") (pin "19") (pinfunction "(SCK)PB5_19") (pintype "bidirectional"))
    )
    (net (code "80") (name "unconnected-(ZU4-AREF-Pad21)") (class "Default")
      (node (ref "ZU4") (pin "21") (pinfunction "AREF_21") (pintype "passive"))
    )
  )
)
